# RHX-NYFK-SCH21V1_01.net
KiCad netlist of a schematic drawn in Altium Designer
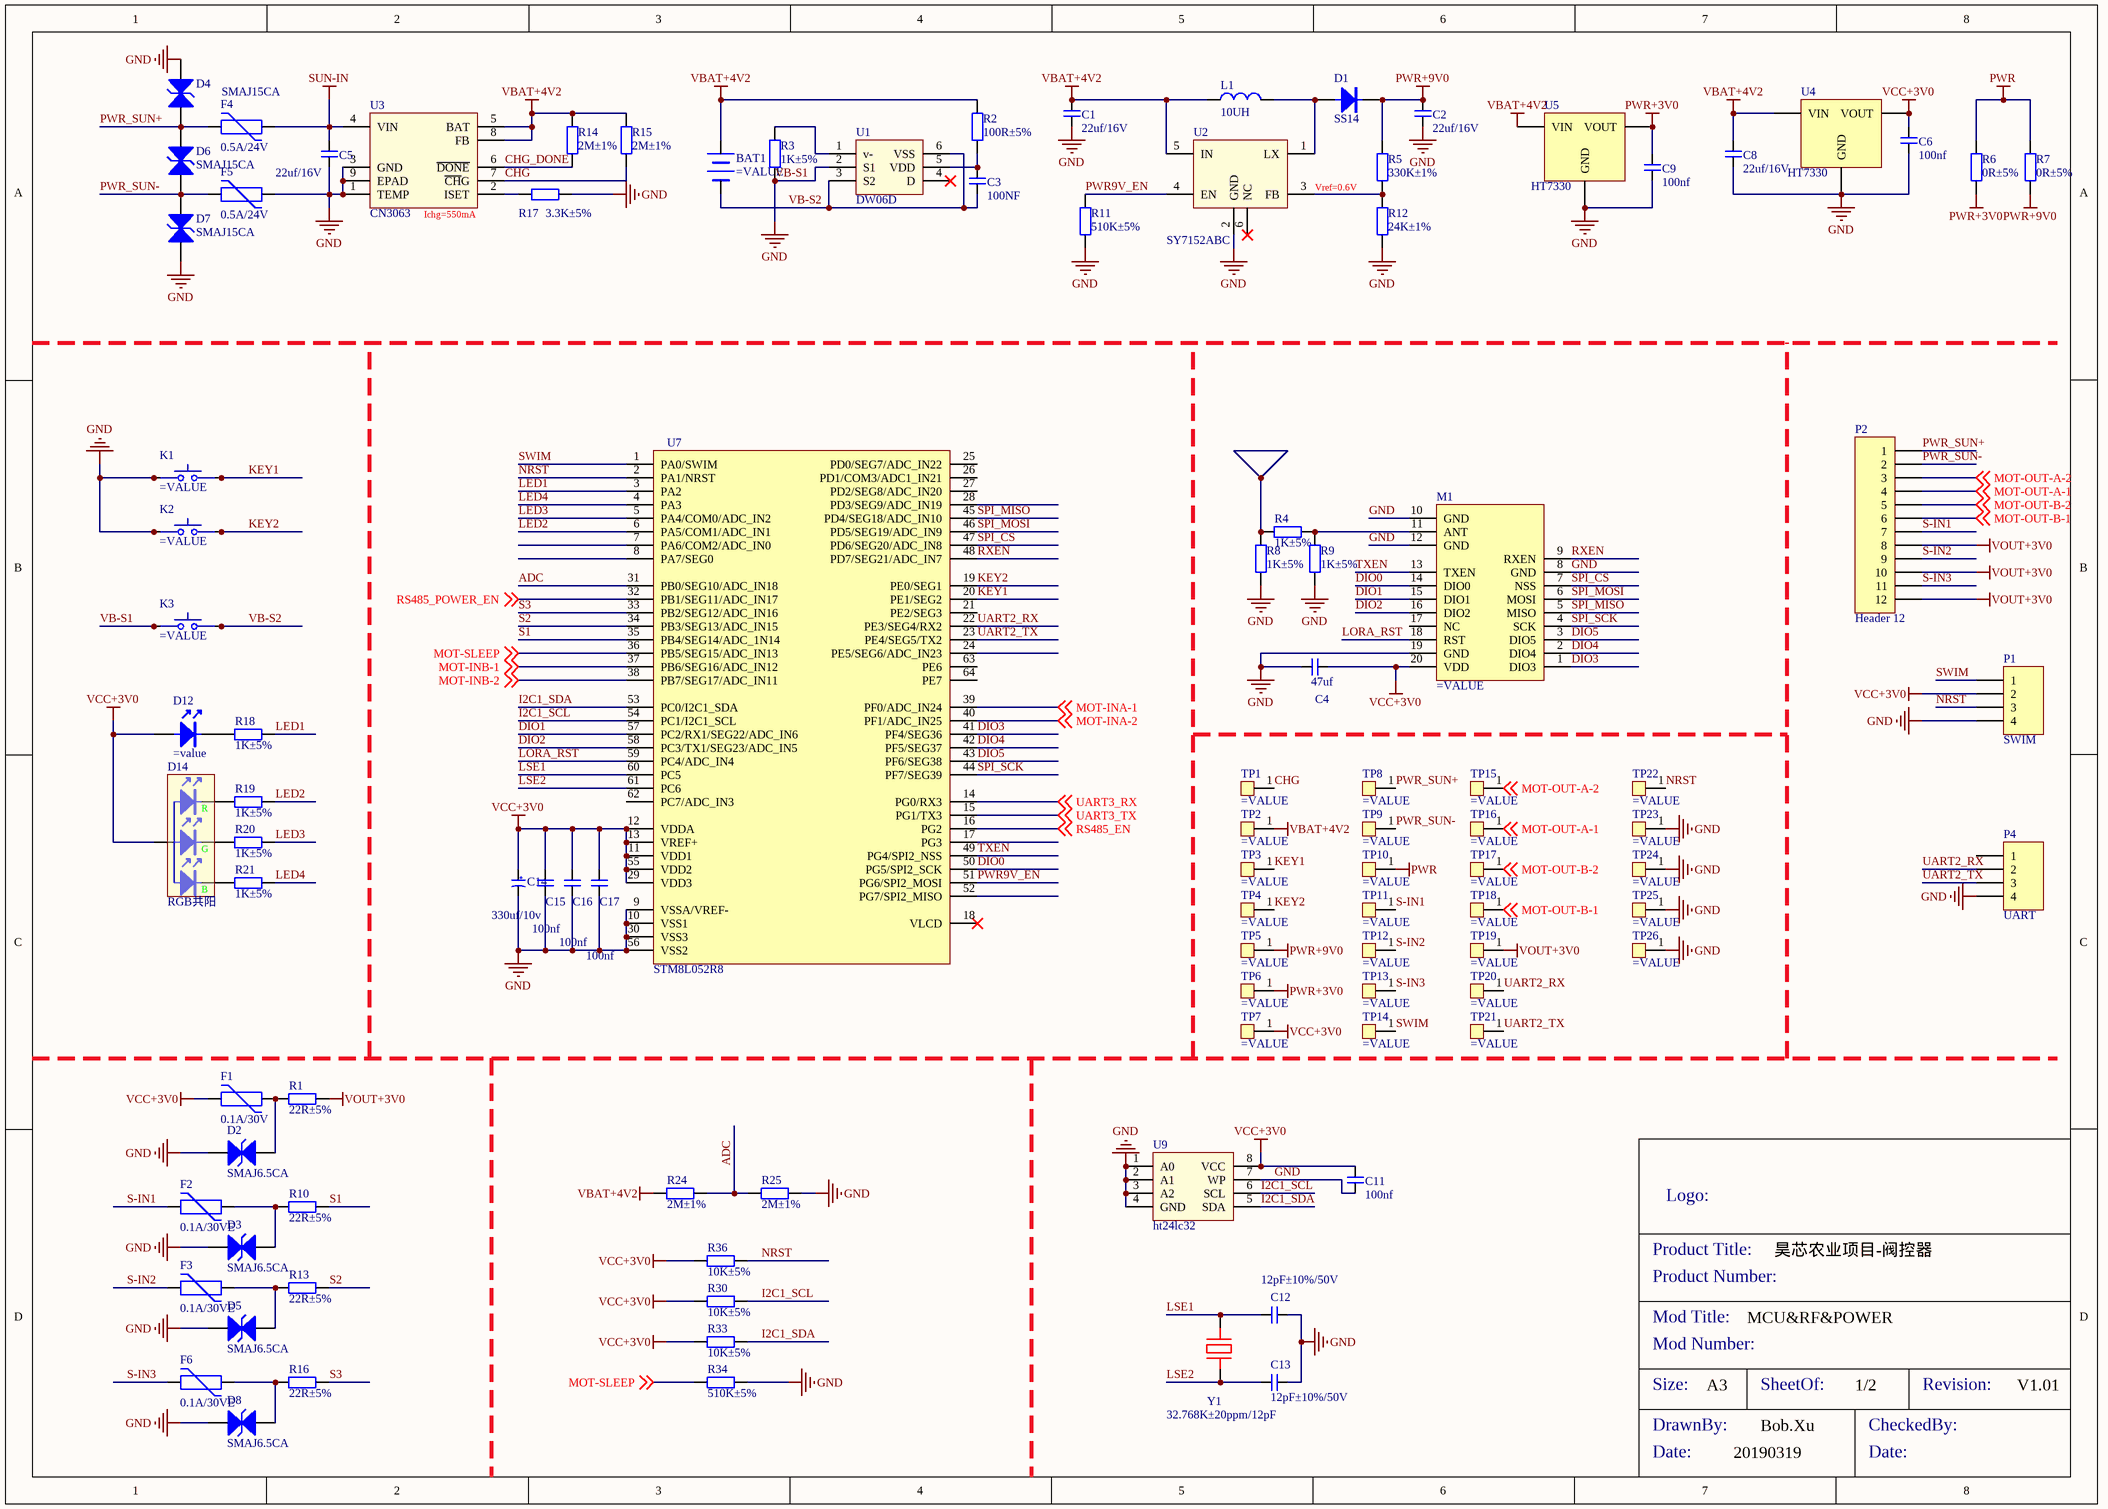
[diagram p0: RHX-NYFK-SCH21V1.01.SchDoc]

(export (version "E")
  (design (tool "Eeschema 10.0.6"))
  (components
    (comp (ref "BAT1") (value "~") (footprint "HDR1X2") (libsource (lib "瑞臻信息") (part "BAT")))
    (comp (ref "C1")
      (value "22uf/16V")
      (footprint "瑞臻信息:c1206")
      (description "无极性电容")
      (libsource (lib "瑞臻信息") (part "无极性电容"))
    )
    (comp (ref "C2")
      (value "22uf/16V")
      (footprint "瑞臻信息:c1206")
      (description "无极性电容")
      (libsource (lib "瑞臻信息") (part "无极性电容"))
    )
    (comp (ref "C3")
      (value "100NF")
      (footprint "C0402")
      (description "无极性电容")
      (libsource (lib "瑞臻信息") (part "无极性电容"))
    )
    (comp (ref "C4")
      (value "47uf")
      (footprint "瑞臻信息:C1206")
      (description "无极性电容")
      (libsource (lib "瑞臻信息") (part "无极性电容"))
    )
    (comp (ref "C5")
      (value "22uf/16V")
      (footprint "瑞臻信息:c1206")
      (description "无极性电容")
      (libsource (lib "瑞臻信息") (part "无极性电容"))
    )
    (comp (ref "C6")
      (value "100nf")
      (footprint "瑞臻信息:c0402")
      (description "无极性电容")
      (libsource (lib "瑞臻信息") (part "无极性电容"))
    )
    (comp (ref "C8")
      (value "22uf/16V")
      (footprint "瑞臻信息:c1206")
      (description "无极性电容")
      (libsource (lib "瑞臻信息") (part "无极性电容"))
    )
    (comp (ref "C9")
      (value "100nf")
      (footprint "瑞臻信息:c0402")
      (description "无极性电容")
      (libsource (lib "瑞臻信息") (part "无极性电容"))
    )
    (comp (ref "C11")
      (value "100nf")
      (footprint "C0402")
      (description "无极性电容")
      (libsource (lib "瑞臻信息") (part "无极性电容"))
    )
    (comp (ref "C12")
      (value "12pF±10%/50V")
      (footprint "C0402")
      (description "无极性电容")
      (libsource (lib "瑞臻信息") (part "无极性电容"))
    )
    (comp (ref "C13")
      (value "12pF±10%/50V")
      (footprint "C0402")
      (description "无极性电容")
      (libsource (lib "瑞臻信息") (part "无极性电容"))
    )
    (comp (ref "C14")
      (value "330uf/10v")
      (footprint "CAP_2P_2R5_D6R3H11_W")
      (description "极性电容")
      (libsource (lib "瑞臻信息") (part "极性电容"))
    )
    (comp (ref "C15")
      (value "100nf")
      (footprint "C0402")
      (description "无极性电容")
      (libsource (lib "瑞臻信息") (part "无极性电容"))
    )
    (comp (ref "C16")
      (value "100nf")
      (footprint "C0402")
      (description "无极性电容")
      (libsource (lib "瑞臻信息") (part "无极性电容"))
    )
    (comp (ref "C17")
      (value "100nf")
      (footprint "C0402")
      (description "无极性电容")
      (libsource (lib "瑞臻信息") (part "无极性电容"))
    )
    (comp (ref "D1")
      (value "SS14")
      (footprint "SMA_2P_2R8X4R6")
      (description "普通二极管")
      (libsource (lib "瑞臻信息") (part "普通二极管"))
    )
    (comp (ref "D2")
      (value "SMAJ6.5CA")
      (footprint "SMA_2P_2R8X4R6")
      (description "双向TVS管")
      (libsource (lib "瑞臻信息") (part "双向TVS管"))
    )
    (comp (ref "D3")
      (value "SMAJ6.5CA")
      (footprint "SMA_2P_2R8X4R6")
      (description "双向TVS管")
      (libsource (lib "瑞臻信息") (part "双向TVS管"))
    )
    (comp (ref "D4")
      (value "SMAJ15CA")
      (footprint "SMA_2P_2R8X4R6")
      (description "双向TVS管")
      (libsource (lib "瑞臻信息") (part "双向TVS管"))
    )
    (comp (ref "D5")
      (value "SMAJ6.5CA")
      (footprint "SMA_2P_2R8X4R6")
      (description "双向TVS管")
      (libsource (lib "瑞臻信息") (part "双向TVS管"))
    )
    (comp (ref "D6")
      (value "SMAJ15CA")
      (footprint "SMA_2P_2R8X4R6")
      (description "双向TVS管")
      (libsource (lib "瑞臻信息") (part "双向TVS管"))
    )
    (comp (ref "D7")
      (value "SMAJ15CA")
      (footprint "SMA_2P_2R8X4R6")
      (description "双向TVS管")
      (libsource (lib "瑞臻信息") (part "双向TVS管"))
    )
    (comp (ref "D8")
      (value "SMAJ6.5CA")
      (footprint "SMA_2P_2R8X4R6")
      (description "双向TVS管")
      (libsource (lib "瑞臻信息") (part "双向TVS管"))
    )
    (comp (ref "D12")
      (value "~")
      (footprint "LED_2P_2R54_D5X8R7")
      (description "单LED")
      (libsource (lib "瑞臻信息") (part "单LED"))
    )
    (comp (ref "D14")
      (value "RGB共阳")
      (footprint "DIP_LED_4P_RGB_1R3_D5")
      (libsource (lib "瑞臻信息") (part "LED-RGB-共阳"))
    )
    (comp (ref "F1") (value "0.1A/30V") (footprint "FUSE1210") (libsource (lib "瑞臻信息") (part "PPTC")))
    (comp (ref "F2") (value "0.1A/30VE") (footprint "FUSE1210") (libsource (lib "瑞臻信息") (part "PPTC")))
    (comp (ref "F3") (value "0.1A/30VE") (footprint "FUSE1210") (libsource (lib "瑞臻信息") (part "PPTC")))
    (comp (ref "F4") (value "0.5A/24V") (footprint "FUSE1210") (libsource (lib "瑞臻信息") (part "PPTC")))
    (comp (ref "F5") (value "0.5A/24V") (footprint "FUSE1210") (libsource (lib "瑞臻信息") (part "PPTC")))
    (comp (ref "F6") (value "0.1A/30VE") (footprint "FUSE1210") (libsource (lib "瑞臻信息") (part "PPTC")))
    (comp (ref "K1")
      (value "~")
      (footprint "DIP_SW_4P_6R0X6R0_P")
      (description "4脚贴片按键")
      (libsource (lib "瑞臻信息") (part "SKRWAEE030"))
    )
    (comp (ref "K2")
      (value "~")
      (footprint "DIP_SW_4P_6R0X6R0_P")
      (description "4脚贴片按键")
      (libsource (lib "瑞臻信息") (part "SKRWAEE030"))
    )
    (comp (ref "K3")
      (value "~")
      (footprint "DIP_SW_4P_6R0X6R0_P")
      (description "4脚贴片按键")
      (libsource (lib "瑞臻信息") (part "SKRWAEE030"))
    )
    (comp (ref "L1")
      (value "10UH")
      (footprint "SMD_INC_2P_4R0X4R0")
      (description "普通电感")
      (libsource (lib "瑞臻信息") (part "普通电感"))
    )
    (comp (ref "M1") (value "~") (footprint "LORA_PIN_1") (libsource (lib "瑞臻信息") (part "LORA_PIN_1")))
    (comp (ref "P1")
      (value "SWIM")
      (footprint "HDR1X4")
      (description "Header, 4-Pin")
      (libsource (lib "Miscellaneous Connectors") (part "Header 4"))
    )
    (comp (ref "P2")
      (value "Header 12")
      (footprint "KF301_12P_5R08")
      (description "Header, 12-Pin")
      (libsource (lib "Miscellaneous Connectors") (part "Header 12"))
    )
    (comp (ref "P4")
      (value "UART")
      (footprint "HDR1X4")
      (description "Header, 4-Pin")
      (libsource (lib "Miscellaneous Connectors") (part "Header 4"))
    )
    (comp (ref "R1")
      (value "22R±5%")
      (footprint "R0402")
      (description "电阻-4.7R±5%-1/16W-0402")
      (fields (field (name "PART NUMBER") "1.2.03.01.0573"))
      (libsource (lib "檀木科技") (part "普通电阻"))
    )
    (comp (ref "R2")
      (value "100R±5%")
      (footprint "R0402")
      (description "电阻-4.7R±5%-1/16W-0402")
      (fields (field (name "PART NUMBER") "1.2.03.01.0573"))
      (libsource (lib "") (part "普通电阻_2"))
    )
    (comp (ref "R3")
      (value "1K±5%")
      (footprint "R0402")
      (description "电阻-4.7R±5%-1/16W-0402")
      (fields (field (name "PART NUMBER") "1.2.03.01.0573"))
      (libsource (lib "") (part "普通电阻_2"))
    )
    (comp (ref "R4")
      (value "1K±5%")
      (footprint "R0402")
      (description "电阻-10K±5%-1/16W-0402")
      (fields (field (name "PART NUMBER") "1.2.03.01.0012"))
      (libsource (lib "") (part "普通电阻_2"))
    )
    (comp (ref "R5")
      (value "330K±1%")
      (footprint "R0402")
      (description "电阻-10K±5%-1/16W-0402")
      (fields (field (name "PART NUMBER") "1.2.03.01.0012"))
      (libsource (lib "") (part "普通电阻_2"))
    )
    (comp (ref "R6")
      (value "0R±5%")
      (footprint "R0603")
      (description "电阻-10K±5%-1/16W-0402")
      (fields (field (name "PART NUMBER") "1.2.03.01.0012"))
      (libsource (lib "") (part "普通电阻_2"))
    )
    (comp (ref "R7")
      (value "0R±5%")
      (footprint "R0603")
      (description "电阻-10K±5%-1/16W-0402")
      (fields (field (name "PART NUMBER") "1.2.03.01.0012"))
      (libsource (lib "") (part "普通电阻_2"))
    )
    (comp (ref "R8")
      (value "1K±5%")
      (footprint "R0402")
      (description "电阻-10K±5%-1/16W-0402")
      (fields (field (name "PART NUMBER") "1.2.03.01.0012"))
      (libsource (lib "檀木科技") (part "普通电阻"))
    )
    (comp (ref "R9")
      (value "1K±5%")
      (footprint "R0402")
      (description "电阻-10K±5%-1/16W-0402")
      (fields (field (name "PART NUMBER") "1.2.03.01.0012"))
      (libsource (lib "檀木科技") (part "普通电阻"))
    )
    (comp (ref "R10")
      (value "22R±5%")
      (footprint "R0402")
      (description "电阻-4.7R±5%-1/16W-0402")
      (fields (field (name "PART NUMBER") "1.2.03.01.0573"))
      (libsource (lib "檀木科技") (part "普通电阻"))
    )
    (comp (ref "R11")
      (value "510K±5%")
      (footprint "R0402")
      (description "电阻-10K±5%-1/16W-0402")
      (fields (field (name "PART NUMBER") "1.2.03.01.0012"))
      (libsource (lib "") (part "普通电阻_2"))
    )
    (comp (ref "R12")
      (value "24K±1%")
      (footprint "R0402")
      (description "电阻-10K±5%-1/16W-0402")
      (fields (field (name "PART NUMBER") "1.2.03.01.0012"))
      (libsource (lib "") (part "普通电阻_2"))
    )
    (comp (ref "R13")
      (value "22R±5%")
      (footprint "R0402")
      (description "电阻-4.7R±5%-1/16W-0402")
      (fields (field (name "PART NUMBER") "1.2.03.01.0573"))
      (libsource (lib "檀木科技") (part "普通电阻"))
    )
    (comp (ref "R14")
      (value "2M±1%")
      (footprint "R0402")
      (description "电阻-10K±5%-1/16W-0402")
      (fields (field (name "PART NUMBER") "1.2.03.01.0012"))
      (libsource (lib "") (part "普通电阻_3"))
    )
    (comp (ref "R15")
      (value "2M±1%")
      (footprint "R0402")
      (description "电阻-10K±5%-1/16W-0402")
      (fields (field (name "PART NUMBER") "1.2.03.01.0012"))
      (libsource (lib "") (part "普通电阻_3"))
    )
    (comp (ref "R16")
      (value "22R±5%")
      (footprint "R0402")
      (description "电阻-4.7R±5%-1/16W-0402")
      (fields (field (name "PART NUMBER") "1.2.03.01.0573"))
      (libsource (lib "檀木科技") (part "普通电阻"))
    )
    (comp (ref "R17")
      (value "3.3K±5%")
      (footprint "R0402")
      (description "电阻-4.7R±5%-1/16W-0402")
      (fields (field (name "PART NUMBER") "1.2.03.01.0573"))
      (libsource (lib "") (part "普通电阻_1"))
    )
    (comp (ref "R18")
      (value "1K±5%")
      (footprint "R0402")
      (description "电阻-4.7R±5%-1/16W-0402")
      (fields (field (name "PART NUMBER") "1.2.03.01.0573"))
      (libsource (lib "檀木科技") (part "普通电阻"))
    )
    (comp (ref "R19")
      (value "1K±5%")
      (footprint "R0402")
      (description "电阻-4.7R±5%-1/16W-0402")
      (fields (field (name "PART NUMBER") "1.2.03.01.0573"))
      (libsource (lib "檀木科技") (part "普通电阻"))
    )
    (comp (ref "R20")
      (value "1K±5%")
      (footprint "R0402")
      (description "电阻-4.7R±5%-1/16W-0402")
      (fields (field (name "PART NUMBER") "1.2.03.01.0573"))
      (libsource (lib "檀木科技") (part "普通电阻"))
    )
    (comp (ref "R21")
      (value "1K±5%")
      (footprint "R0402")
      (description "电阻-4.7R±5%-1/16W-0402")
      (fields (field (name "PART NUMBER") "1.2.03.01.0573"))
      (libsource (lib "檀木科技") (part "普通电阻"))
    )
    (comp (ref "R24")
      (value "2M±1%")
      (footprint "R0402")
      (description "电阻-10K±5%-1/16W-0402")
      (fields (field (name "PART NUMBER") "1.2.03.01.0012"))
      (libsource (lib "") (part "普通电阻_1"))
    )
    (comp (ref "R25")
      (value "2M±1%")
      (footprint "R0402")
      (description "电阻-10K±5%-1/16W-0402")
      (fields (field (name "PART NUMBER") "1.2.03.01.0012"))
      (libsource (lib "") (part "普通电阻_1"))
    )
    (comp (ref "R30")
      (value "10K±5%")
      (footprint "R0402")
      (description "电阻-10K±5%-1/16W-0402")
      (fields (field (name "PART NUMBER") "1.2.03.01.0012"))
      (libsource (lib "檀木科技") (part "普通电阻"))
    )
    (comp (ref "R33")
      (value "10K±5%")
      (footprint "R0402")
      (description "电阻-10K±5%-1/16W-0402")
      (fields (field (name "PART NUMBER") "1.2.03.01.0012"))
      (libsource (lib "檀木科技") (part "普通电阻"))
    )
    (comp (ref "R34")
      (value "510K±5%")
      (footprint "R0402")
      (description "电阻-10K±5%-1/16W-0402")
      (fields (field (name "PART NUMBER") "1.2.03.01.0012"))
      (libsource (lib "檀木科技") (part "普通电阻"))
    )
    (comp (ref "R36")
      (value "10K±5%")
      (footprint "R0402")
      (description "电阻-10K±5%-1/16W-0402")
      (fields (field (name "PART NUMBER") "1.2.03.01.0012"))
      (libsource (lib "檀木科技") (part "普通电阻"))
    )
    (comp (ref "TP1")
      (value "~")
      (footprint "TP_D1R25")
      (description "测试点")
      (libsource (lib "瑞臻信息") (part "Test_Point"))
    )
    (comp (ref "TP2")
      (value "~")
      (footprint "TP_D1R25")
      (description "测试点")
      (libsource (lib "瑞臻信息") (part "Test_Point"))
    )
    (comp (ref "TP3")
      (value "~")
      (footprint "TP_D1R25")
      (description "测试点")
      (libsource (lib "瑞臻信息") (part "Test_Point"))
    )
    (comp (ref "TP4")
      (value "~")
      (footprint "TP_D1R25")
      (description "测试点")
      (libsource (lib "瑞臻信息") (part "Test_Point"))
    )
    (comp (ref "TP5")
      (value "~")
      (footprint "TP_D1R25")
      (description "测试点")
      (libsource (lib "瑞臻信息") (part "Test_Point"))
    )
    (comp (ref "TP6")
      (value "~")
      (footprint "TP_D1R25")
      (description "测试点")
      (libsource (lib "瑞臻信息") (part "Test_Point"))
    )
    (comp (ref "TP7")
      (value "~")
      (footprint "TP_D1R25")
      (description "测试点")
      (libsource (lib "瑞臻信息") (part "Test_Point"))
    )
    (comp (ref "TP8")
      (value "~")
      (footprint "TP_D1R25")
      (description "测试点")
      (libsource (lib "瑞臻信息") (part "Test_Point"))
    )
    (comp (ref "TP9")
      (value "~")
      (footprint "TP_D1R25")
      (description "测试点")
      (libsource (lib "瑞臻信息") (part "Test_Point"))
    )
    (comp (ref "TP10")
      (value "~")
      (footprint "TP_D1R25")
      (description "测试点")
      (libsource (lib "瑞臻信息") (part "Test_Point"))
    )
    (comp (ref "TP11")
      (value "~")
      (footprint "TP_D1R25")
      (description "测试点")
      (libsource (lib "瑞臻信息") (part "Test_Point"))
    )
    (comp (ref "TP12")
      (value "~")
      (footprint "TP_D1R25")
      (description "测试点")
      (libsource (lib "瑞臻信息") (part "Test_Point"))
    )
    (comp (ref "TP13")
      (value "~")
      (footprint "TP_D1R25")
      (description "测试点")
      (libsource (lib "瑞臻信息") (part "Test_Point"))
    )
    (comp (ref "TP14")
      (value "~")
      (footprint "TP_D1R25")
      (description "测试点")
      (libsource (lib "瑞臻信息") (part "Test_Point"))
    )
    (comp (ref "TP15")
      (value "~")
      (footprint "TP_D1R25")
      (description "测试点")
      (libsource (lib "瑞臻信息") (part "Test_Point"))
    )
    (comp (ref "TP16")
      (value "~")
      (footprint "TP_D1R25")
      (description "测试点")
      (libsource (lib "瑞臻信息") (part "Test_Point"))
    )
    (comp (ref "TP17")
      (value "~")
      (footprint "TP_D1R25")
      (description "测试点")
      (libsource (lib "瑞臻信息") (part "Test_Point"))
    )
    (comp (ref "TP18")
      (value "~")
      (footprint "TP_D1R25")
      (description "测试点")
      (libsource (lib "瑞臻信息") (part "Test_Point"))
    )
    (comp (ref "TP19")
      (value "~")
      (footprint "TP_D1R25")
      (description "测试点")
      (libsource (lib "瑞臻信息") (part "Test_Point"))
    )
    (comp (ref "TP20")
      (value "~")
      (footprint "TP_D1R25")
      (description "测试点")
      (libsource (lib "瑞臻信息") (part "Test_Point"))
    )
    (comp (ref "TP21")
      (value "~")
      (footprint "TP_D1R25")
      (description "测试点")
      (libsource (lib "瑞臻信息") (part "Test_Point"))
    )
    (comp (ref "TP22")
      (value "~")
      (footprint "TP_D1R25")
      (description "测试点")
      (libsource (lib "瑞臻信息") (part "Test_Point"))
    )
    (comp (ref "TP23")
      (value "~")
      (footprint "TP_D1R25")
      (description "测试点")
      (libsource (lib "瑞臻信息") (part "Test_Point"))
    )
    (comp (ref "TP24")
      (value "~")
      (footprint "TP_D1R25")
      (description "测试点")
      (libsource (lib "瑞臻信息") (part "Test_Point"))
    )
    (comp (ref "TP25")
      (value "~")
      (footprint "TP_D1R25")
      (description "测试点")
      (libsource (lib "瑞臻信息") (part "Test_Point"))
    )
    (comp (ref "TP26")
      (value "~")
      (footprint "TP_D1R25")
      (description "测试点")
      (libsource (lib "瑞臻信息") (part "Test_Point"))
    )
    (comp (ref "U1")
      (value "DW06D")
      (footprint "SOT23_6P_0R95_1R6X2R9")
      (libsource (lib "瑞臻信息") (part "DW06D"))
    )
    (comp (ref "U2")
      (value "SY7152ABC")
      (footprint "SOT23_6P_0R95_1R6X2R9")
      (libsource (lib "瑞臻信息") (part "SY7152"))
    )
    (comp (ref "U3")
      (value "CN3063")
      (footprint "SOP_8P_1R27_3R9X4R9_P")
      (libsource (lib "瑞臻信息") (part "CN3063"))
    )
    (comp (ref "U4")
      (value "HT7330")
      (footprint "SOT89_3P_1R5_2R5X4R5")
      (libsource (lib "瑞臻信息") (part "HT73XX"))
    )
    (comp (ref "U5")
      (value "HT7330")
      (footprint "SOT89_3P_1R5_2R5X4R5")
      (libsource (lib "瑞臻信息") (part "HT73XX"))
    )
    (comp (ref "U7")
      (value "STM8L052R8")
      (footprint "LQFP_64P_0R5_10R0X10R0")
      (description "MCU_STM8L052R8_16MHz_Flash/64Kb_RAM/4Kb_8位_E2PROM/256B_LCD8X24_LQFP64")
      (fields (field (name "PART NUMBER") "1.2.18.01.0001"))
      (libsource (lib "瑞臻信息") (part "STM8L052R8"))
    )
    (comp (ref "U9")
      (value "ht24lc32")
      (footprint "SOP_8P_1R27_3R9X4R9")
      (libsource (lib "瑞臻信息") (part "24CXX"))
    )
    (comp (ref "Y1")
      (value "32.768K±20ppm/12pF")
      (footprint "SMD_Crystal_2P_1R5X3R2")
      (description "两脚晶体谐振器")
      (libsource (lib "瑞臻信息") (part "两脚晶体谐振器"))
    )
  )
  (nets
    (net (code "1") (name "/ADC") (class "Default")
      (node (ref "R24") (pin "2") (pinfunction "2_2") (pintype "passive"))
      (node (ref "R25") (pin "1") (pinfunction "1_1") (pintype "passive"))
      (node (ref "U7") (pin "31") (pinfunction "PB0/SEG10/ADC_IN18_31") (pintype "passive"))
    )
    (net (code "2") (name "/CHG") (class "Default")
      (node (ref "R15") (pin "1") (pinfunction "1_1") (pintype "passive"))
      (node (ref "TP1") (pin "1") (pinfunction "1_1") (pintype "passive"))
      (node (ref "U3") (pin "7") (pinfunction "~{CH}G_7") (pintype "passive"))
    )
    (net (code "3") (name "/CHG_DONE") (class "Default")
      (node (ref "R14") (pin "1") (pinfunction "1_1") (pintype "passive"))
      (node (ref "U3") (pin "6") (pinfunction "~{DONE}_6") (pintype "passive"))
    )
    (net (code "4") (name "/DIO0") (class "Default")
      (node (ref "M1") (pin "14") (pinfunction "DIO0_14") (pintype "passive"))
      (node (ref "U7") (pin "50") (pinfunction "PG5/SPI2_SCK_50") (pintype "passive"))
    )
    (net (code "5") (name "/DIO1") (class "Default")
      (node (ref "M1") (pin "15") (pinfunction "DIO1_15") (pintype "passive"))
      (node (ref "U7") (pin "57") (pinfunction "PC2/RX1/SEG22/ADC_IN6_57") (pintype "passive"))
    )
    (net (code "6") (name "/DIO2") (class "Default")
      (node (ref "M1") (pin "16") (pinfunction "DIO2_16") (pintype "passive"))
      (node (ref "U7") (pin "58") (pinfunction "PC3/TX1/SEG23/ADC_IN5_58") (pintype "passive"))
    )
    (net (code "7") (name "/DIO3") (class "Default")
      (node (ref "M1") (pin "1") (pinfunction "DIO3_1") (pintype "passive"))
      (node (ref "U7") (pin "41") (pinfunction "PF4/SEG36_41") (pintype "passive"))
    )
    (net (code "8") (name "/DIO4") (class "Default")
      (node (ref "M1") (pin "2") (pinfunction "DIO4_2") (pintype "passive"))
      (node (ref "U7") (pin "42") (pinfunction "PF5/SEG37_42") (pintype "passive"))
    )
    (net (code "9") (name "/DIO5") (class "Default")
      (node (ref "M1") (pin "3") (pinfunction "DIO5_3") (pintype "passive"))
      (node (ref "U7") (pin "43") (pinfunction "PF6/SEG38_43") (pintype "passive"))
    )
    (net (code "10") (name "/I2C1_SCL") (class "Default")
      (node (ref "R30") (pin "1") (pinfunction "1_1") (pintype "passive"))
      (node (ref "U7") (pin "54") (pinfunction "PC1/I2C1_SCL_54") (pintype "passive"))
      (node (ref "U9") (pin "6") (pinfunction "SCL_6") (pintype "passive"))
    )
    (net (code "11") (name "/I2C1_SDA") (class "Default")
      (node (ref "R33") (pin "1") (pinfunction "1_1") (pintype "passive"))
      (node (ref "U7") (pin "53") (pinfunction "PC0/I2C1_SDA_53") (pintype "passive"))
      (node (ref "U9") (pin "5") (pinfunction "SDA_5") (pintype "passive"))
    )
    (net (code "12") (name "/KEY1") (class "Default")
      (node (ref "K1") (pin "2") (pinfunction "2_2") (pintype "passive"))
      (node (ref "K1") (pin "4") (pinfunction "4_4") (pintype "passive"))
      (node (ref "TP3") (pin "1") (pinfunction "1_1") (pintype "passive"))
      (node (ref "U7") (pin "20") (pinfunction "PE1/SEG2_20") (pintype "passive"))
    )
    (net (code "13") (name "/KEY2") (class "Default")
      (node (ref "K2") (pin "2") (pinfunction "2_2") (pintype "passive"))
      (node (ref "K2") (pin "4") (pinfunction "4_4") (pintype "passive"))
      (node (ref "TP4") (pin "1") (pinfunction "1_1") (pintype "passive"))
      (node (ref "U7") (pin "19") (pinfunction "PE0/SEG1_19") (pintype "passive"))
    )
    (net (code "14") (name "/LED1") (class "Default")
      (node (ref "R18") (pin "1") (pinfunction "1_1") (pintype "passive"))
      (node (ref "U7") (pin "3") (pinfunction "PA2_3") (pintype "passive"))
    )
    (net (code "15") (name "/LED2") (class "Default")
      (node (ref "R19") (pin "1") (pinfunction "1_1") (pintype "passive"))
      (node (ref "U7") (pin "6") (pinfunction "PA5/COM1/ADC_IN1_6") (pintype "passive"))
    )
    (net (code "16") (name "/LED3") (class "Default")
      (node (ref "R20") (pin "1") (pinfunction "1_1") (pintype "passive"))
      (node (ref "U7") (pin "5") (pinfunction "PA4/COM0/ADC_IN2_5") (pintype "passive"))
    )
    (net (code "17") (name "/LED4") (class "Default")
      (node (ref "R21") (pin "1") (pinfunction "1_1") (pintype "passive"))
      (node (ref "U7") (pin "4") (pinfunction "PA3_4") (pintype "passive"))
    )
    (net (code "18") (name "/LORA_RST") (class "Default")
      (node (ref "M1") (pin "18") (pinfunction "RST_18") (pintype "passive"))
      (node (ref "U7") (pin "59") (pinfunction "PC4/ADC_IN4_59") (pintype "passive"))
    )
    (net (code "19") (name "/LSE1") (class "Default")
      (node (ref "C12") (pin "2") (pinfunction "2_2") (pintype "passive"))
      (node (ref "U7") (pin "60") (pinfunction "PC5_60") (pintype "passive"))
      (node (ref "Y1") (pin "2") (pinfunction "2_2") (pintype "passive"))
    )
    (net (code "20") (name "/LSE2") (class "Default")
      (node (ref "C13") (pin "2") (pinfunction "2_2") (pintype "passive"))
      (node (ref "U7") (pin "61") (pinfunction "PC6_61") (pintype "passive"))
      (node (ref "Y1") (pin "1") (pinfunction "1_1") (pintype "passive"))
    )
    (net (code "21") (name "/NRST") (class "Default")
      (node (ref "P1") (pin "3") (pinfunction "3_3") (pintype "passive"))
      (node (ref "R36") (pin "1") (pinfunction "1_1") (pintype "passive"))
      (node (ref "TP22") (pin "1") (pinfunction "1_1") (pintype "passive"))
      (node (ref "U7") (pin "2") (pinfunction "PA1/NRST_2") (pintype "passive"))
    )
    (net (code "22") (name "/PWR9V_EN") (class "Default")
      (node (ref "R11") (pin "1") (pinfunction "1_1") (pintype "passive"))
      (node (ref "U2") (pin "4") (pinfunction "EN_4") (pintype "passive"))
      (node (ref "U7") (pin "51") (pinfunction "PG6/SPI2_MOSI_51") (pintype "passive"))
    )
    (net (code "23") (name "/PWR_SUN+") (class "Default")
      (node (ref "D4") (pin "1") (pinfunction "A_1") (pintype "passive"))
      (node (ref "D6") (pin "2") (pinfunction "K_2") (pintype "passive"))
      (node (ref "F4") (pin "1") (pinfunction "1_1") (pintype "passive"))
      (node (ref "P2") (pin "1") (pinfunction "1_1") (pintype "passive"))
      (node (ref "TP8") (pin "1") (pinfunction "1_1") (pintype "passive"))
    )
    (net (code "24") (name "/PWR_SUN-") (class "Default")
      (node (ref "D6") (pin "1") (pinfunction "A_1") (pintype "passive"))
      (node (ref "D7") (pin "2") (pinfunction "K_2") (pintype "passive"))
      (node (ref "F5") (pin "1") (pinfunction "1_1") (pintype "passive"))
      (node (ref "P2") (pin "2") (pinfunction "2_2") (pintype "passive"))
      (node (ref "TP9") (pin "1") (pinfunction "1_1") (pintype "passive"))
    )
    (net (code "25") (name "/RXEN") (class "Default")
      (node (ref "M1") (pin "9") (pinfunction "RXEN_9") (pintype "passive"))
      (node (ref "U7") (pin "48") (pinfunction "PD7/SEG21/ADC_IN7_48") (pintype "passive"))
    )
    (net (code "26") (name "/S-IN1") (class "Default")
      (node (ref "F2") (pin "1") (pinfunction "1_1") (pintype "passive"))
      (node (ref "P2") (pin "7") (pinfunction "7_7") (pintype "passive"))
      (node (ref "TP11") (pin "1") (pinfunction "1_1") (pintype "passive"))
    )
    (net (code "27") (name "/S-IN2") (class "Default")
      (node (ref "F3") (pin "1") (pinfunction "1_1") (pintype "passive"))
      (node (ref "P2") (pin "9") (pinfunction "9_9") (pintype "passive"))
      (node (ref "TP12") (pin "1") (pinfunction "1_1") (pintype "passive"))
    )
    (net (code "28") (name "/S-IN3") (class "Default")
      (node (ref "F6") (pin "1") (pinfunction "1_1") (pintype "passive"))
      (node (ref "P2") (pin "11") (pinfunction "11_11") (pintype "passive"))
      (node (ref "TP13") (pin "1") (pinfunction "1_1") (pintype "passive"))
    )
    (net (code "29") (name "/S1") (class "Default")
      (node (ref "R10") (pin "1") (pinfunction "1_1") (pintype "passive"))
      (node (ref "U7") (pin "35") (pinfunction "PB4/SEG14/ADC_1N14_35") (pintype "passive"))
    )
    (net (code "30") (name "/S2") (class "Default")
      (node (ref "R13") (pin "1") (pinfunction "1_1") (pintype "passive"))
      (node (ref "U7") (pin "34") (pinfunction "PB3/SEG13/ADC_IN15_34") (pintype "passive"))
    )
    (net (code "31") (name "/S3") (class "Default")
      (node (ref "R16") (pin "1") (pinfunction "1_1") (pintype "passive"))
      (node (ref "U7") (pin "33") (pinfunction "PB2/SEG12/ADC_IN16_33") (pintype "passive"))
    )
    (net (code "32") (name "/SPI_CS") (class "Default")
      (node (ref "M1") (pin "7") (pinfunction "NSS_7") (pintype "passive"))
      (node (ref "U7") (pin "47") (pinfunction "PD6/SEG20/ADC_IN8_47") (pintype "passive"))
    )
    (net (code "33") (name "/SPI_MISO") (class "Default")
      (node (ref "M1") (pin "5") (pinfunction "MISO_5") (pintype "passive"))
      (node (ref "U7") (pin "45") (pinfunction "PD4/SEG18/ADC_IN10_45") (pintype "passive"))
    )
    (net (code "34") (name "/SPI_MOSI") (class "Default")
      (node (ref "M1") (pin "6") (pinfunction "MOSI_6") (pintype "passive"))
      (node (ref "U7") (pin "46") (pinfunction "PD5/SEG19/ADC_IN9_46") (pintype "passive"))
    )
    (net (code "35") (name "/SPI_SCK") (class "Default")
      (node (ref "M1") (pin "4") (pinfunction "SCK_4") (pintype "passive"))
      (node (ref "U7") (pin "44") (pinfunction "PF7/SEG39_44") (pintype "passive"))
    )
    (net (code "36") (name "/SWIM") (class "Default")
      (node (ref "P1") (pin "1") (pinfunction "1_1") (pintype "passive"))
      (node (ref "TP14") (pin "1") (pinfunction "1_1") (pintype "passive"))
      (node (ref "U7") (pin "1") (pinfunction "PA0/SWIM_1") (pintype "passive"))
    )
    (net (code "37") (name "/TXEN") (class "Default")
      (node (ref "M1") (pin "13") (pinfunction "TXEN_13") (pintype "passive"))
      (node (ref "U7") (pin "49") (pinfunction "PG4/SPI2_NSS_49") (pintype "passive"))
    )
    (net (code "38") (name "/UART2_RX") (class "Default")
      (node (ref "P4") (pin "2") (pinfunction "2_2") (pintype "passive"))
      (node (ref "TP20") (pin "1") (pinfunction "1_1") (pintype "passive"))
      (node (ref "U7") (pin "22") (pinfunction "PE3/SEG4/RX2_22") (pintype "passive"))
    )
    (net (code "39") (name "/UART2_TX") (class "Default")
      (node (ref "P4") (pin "3") (pinfunction "3_3") (pintype "passive"))
      (node (ref "TP21") (pin "1") (pinfunction "1_1") (pintype "passive"))
      (node (ref "U7") (pin "23") (pinfunction "PE4/SEG5/TX2_23") (pintype "passive"))
    )
    (net (code "40") (name "/VB-S2") (class "Default")
      (node (ref "BAT1") (pin "2") (pintype "passive"))
      (node (ref "C3") (pin "1") (pinfunction "1_1") (pintype "passive"))
      (node (ref "K3") (pin "2") (pinfunction "2_2") (pintype "passive"))
      (node (ref "K3") (pin "4") (pinfunction "4_4") (pintype "passive"))
      (node (ref "U1") (pin "3") (pinfunction "S2_3") (pintype "passive"))
      (node (ref "U1") (pin "6") (pinfunction "VSS_6") (pintype "passive"))
    )
    (net (code "41") (name "GND") (class "Default")
      (node (ref "C1") (pin "1") (pinfunction "1_1") (pintype "passive"))
      (node (ref "C11") (pin "1") (pinfunction "1_1") (pintype "passive"))
      (node (ref "C12") (pin "1") (pinfunction "1_1") (pintype "passive"))
      (node (ref "C13") (pin "1") (pinfunction "1_1") (pintype "passive"))
      (node (ref "C14") (pin "2") (pinfunction "2_2") (pintype "passive"))
      (node (ref "C15") (pin "1") (pinfunction "1_1") (pintype "passive"))
      (node (ref "C16") (pin "1") (pinfunction "1_1") (pintype "passive"))
      (node (ref "C17") (pin "1") (pinfunction "1_1") (pintype "passive"))
      (node (ref "C2") (pin "1") (pinfunction "1_1") (pintype "passive"))
      (node (ref "C4") (pin "1") (pinfunction "1_1") (pintype "passive"))
      (node (ref "C5") (pin "1") (pinfunction "1_1") (pintype "passive"))
      (node (ref "C6") (pin "1") (pinfunction "1_1") (pintype "passive"))
      (node (ref "C8") (pin "1") (pinfunction "1_1") (pintype "passive"))
      (node (ref "C9") (pin "1") (pinfunction "1_1") (pintype "passive"))
      (node (ref "D2") (pin "1") (pinfunction "A_1") (pintype "passive"))
      (node (ref "D3") (pin "1") (pinfunction "A_1") (pintype "passive"))
      (node (ref "D4") (pin "2") (pinfunction "K_2") (pintype "passive"))
      (node (ref "D5") (pin "1") (pinfunction "A_1") (pintype "passive"))
      (node (ref "D7") (pin "1") (pinfunction "A_1") (pintype "passive"))
      (node (ref "D8") (pin "1") (pinfunction "A_1") (pintype "passive"))
      (node (ref "F5") (pin "2") (pinfunction "2_2") (pintype "passive"))
      (node (ref "K1") (pin "1") (pinfunction "1_1") (pintype "passive"))
      (node (ref "K1") (pin "3") (pinfunction "3_3") (pintype "passive"))
      (node (ref "K2") (pin "1") (pinfunction "1_1") (pintype "passive"))
      (node (ref "K2") (pin "3") (pinfunction "3_3") (pintype "passive"))
      (node (ref "K3") (pin "1") (pinfunction "1_1") (pintype "passive"))
      (node (ref "K3") (pin "3") (pinfunction "3_3") (pintype "passive"))
      (node (ref "M1") (pin "10") (pinfunction "GND_10") (pintype "passive"))
      (node (ref "M1") (pin "12") (pinfunction "GND_12") (pintype "passive"))
      (node (ref "M1") (pin "19") (pinfunction "GND_19") (pintype "passive"))
      (node (ref "M1") (pin "8") (pinfunction "GND_8") (pintype "passive"))
      (node (ref "P1") (pin "4") (pinfunction "4_4") (pintype "passive"))
      (node (ref "P4") (pin "4") (pinfunction "4_4") (pintype "passive"))
      (node (ref "R11") (pin "2") (pinfunction "2_2") (pintype "passive"))
      (node (ref "R12") (pin "2") (pinfunction "2_2") (pintype "passive"))
      (node (ref "R17") (pin "2") (pinfunction "2_2") (pintype "passive"))
      (node (ref "R25") (pin "2") (pinfunction "2_2") (pintype "passive"))
      (node (ref "R3") (pin "2") (pinfunction "2_2") (pintype "passive"))
      (node (ref "R34") (pin "1") (pinfunction "1_1") (pintype "passive"))
      (node (ref "R8") (pin "2") (pinfunction "2_2") (pintype "passive"))
      (node (ref "R9") (pin "2") (pinfunction "2_2") (pintype "passive"))
      (node (ref "TP23") (pin "1") (pinfunction "1_1") (pintype "passive"))
      (node (ref "TP24") (pin "1") (pinfunction "1_1") (pintype "passive"))
      (node (ref "TP25") (pin "1") (pinfunction "1_1") (pintype "passive"))
      (node (ref "TP26") (pin "1") (pinfunction "1_1") (pintype "passive"))
      (node (ref "U1") (pin "2") (pinfunction "S1_2") (pintype "passive"))
      (node (ref "U2") (pin "2") (pinfunction "GND_2") (pintype "passive"))
      (node (ref "U3") (pin "1") (pinfunction "TEMP_1") (pintype "passive"))
      (node (ref "U3") (pin "3") (pinfunction "GND_3") (pintype "passive"))
      (node (ref "U3") (pin "9") (pinfunction "EPAD_9") (pintype "passive"))
      (node (ref "U4") (pin "1") (pinfunction "GND_1") (pintype "passive"))
      (node (ref "U5") (pin "1") (pinfunction "GND_1") (pintype "passive"))
      (node (ref "U7") (pin "10") (pinfunction "VSS1_10") (pintype "passive"))
      (node (ref "U7") (pin "30") (pinfunction "VSS3_30") (pintype "passive"))
      (node (ref "U7") (pin "56") (pinfunction "VSS2_56") (pintype "passive"))
      (node (ref "U7") (pin "9") (pinfunction "VSSA/VREF-_9") (pintype "passive"))
      (node (ref "U9") (pin "1") (pinfunction "A0_1") (pintype "passive"))
      (node (ref "U9") (pin "2") (pinfunction "A1_2") (pintype "passive"))
      (node (ref "U9") (pin "3") (pinfunction "A2_3") (pintype "passive"))
      (node (ref "U9") (pin "4") (pinfunction "GND_4") (pintype "passive"))
      (node (ref "U9") (pin "7") (pinfunction "WP_7") (pintype "passive"))
    )
    (net (code "42") (name "MOT-INA-1") (class "Default")
      (node (ref "U7") (pin "39") (pinfunction "PF0/ADC_IN24_39") (pintype "passive"))
    )
    (net (code "43") (name "MOT-INA-2") (class "Default")
      (node (ref "U7") (pin "40") (pinfunction "PF1/ADC_IN25_40") (pintype "passive"))
    )
    (net (code "44") (name "MOT-INB-1") (class "Default")
      (node (ref "U7") (pin "37") (pinfunction "PB6/SEG16/ADC_IN12_37") (pintype "passive"))
    )
    (net (code "45") (name "MOT-INB-2") (class "Default")
      (node (ref "U7") (pin "38") (pinfunction "PB7/SEG17/ADC_IN11_38") (pintype "passive"))
    )
    (net (code "46") (name "MOT-OUT-A-1") (class "Default")
      (node (ref "P2") (pin "4") (pinfunction "4_4") (pintype "passive"))
      (node (ref "TP16") (pin "1") (pinfunction "1_1") (pintype "passive"))
    )
    (net (code "47") (name "MOT-OUT-A-2") (class "Default")
      (node (ref "P2") (pin "3") (pinfunction "3_3") (pintype "passive"))
      (node (ref "TP15") (pin "1") (pinfunction "1_1") (pintype "passive"))
    )
    (net (code "48") (name "MOT-OUT-B-1") (class "Default")
      (node (ref "P2") (pin "6") (pinfunction "6_6") (pintype "passive"))
      (node (ref "TP18") (pin "1") (pinfunction "1_1") (pintype "passive"))
    )
    (net (code "49") (name "MOT-OUT-B-2") (class "Default")
      (node (ref "P2") (pin "5") (pinfunction "5_5") (pintype "passive"))
      (node (ref "TP17") (pin "1") (pinfunction "1_1") (pintype "passive"))
    )
    (net (code "50") (name "MOT-SLEEP") (class "Default")
      (node (ref "R34") (pin "2") (pinfunction "2_2") (pintype "passive"))
      (node (ref "U7") (pin "36") (pinfunction "PB5/SEG15/ADC_IN13_36") (pintype "passive"))
    )
    (net (code "51") (name "Net-(D1-A)") (class "Default")
      (node (ref "D1") (pin "1") (pinfunction "A_1") (pintype "passive"))
      (node (ref "L1") (pin "2") (pinfunction "2_2") (pintype "passive"))
      (node (ref "U2") (pin "1") (pinfunction "LX_1") (pintype "passive"))
    )
    (net (code "52") (name "Net-(D2-K)") (class "Default")
      (node (ref "D2") (pin "2") (pinfunction "K_2") (pintype "passive"))
      (node (ref "F1") (pin "2") (pinfunction "2_2") (pintype "passive"))
      (node (ref "R1") (pin "2") (pinfunction "2_2") (pintype "passive"))
    )
    (net (code "53") (name "Net-(D3-K)") (class "Default")
      (node (ref "D3") (pin "2") (pinfunction "K_2") (pintype "passive"))
      (node (ref "F2") (pin "2") (pinfunction "2_2") (pintype "passive"))
      (node (ref "R10") (pin "2") (pinfunction "2_2") (pintype "passive"))
    )
    (net (code "54") (name "Net-(D5-K)") (class "Default")
      (node (ref "D5") (pin "2") (pinfunction "K_2") (pintype "passive"))
      (node (ref "F3") (pin "2") (pinfunction "2_2") (pintype "passive"))
      (node (ref "R13") (pin "2") (pinfunction "2_2") (pintype "passive"))
    )
    (net (code "55") (name "Net-(D8-K)") (class "Default")
      (node (ref "D8") (pin "2") (pinfunction "K_2") (pintype "passive"))
      (node (ref "F6") (pin "2") (pinfunction "2_2") (pintype "passive"))
      (node (ref "R16") (pin "2") (pinfunction "2_2") (pintype "passive"))
    )
    (net (code "56") (name "Net-(D12-K)") (class "Default")
      (node (ref "D12") (pin "2") (pinfunction "K_2") (pintype "passive"))
      (node (ref "R18") (pin "2") (pinfunction "2_2") (pintype "passive"))
    )
    (net (code "57") (name "Net-(D14-Pad1)") (class "Default")
      (node (ref "D14") (pin "1") (pinfunction "1_1") (pintype "passive"))
      (node (ref "R19") (pin "2") (pinfunction "2_2") (pintype "passive"))
    )
    (net (code "58") (name "Net-(D14-Pad3)") (class "Default")
      (node (ref "D14") (pin "3") (pinfunction "3_3") (pintype "passive"))
      (node (ref "R20") (pin "2") (pinfunction "2_2") (pintype "passive"))
    )
    (net (code "59") (name "Net-(D14-Pad4)") (class "Default")
      (node (ref "D14") (pin "4") (pinfunction "4_4") (pintype "passive"))
      (node (ref "R21") (pin "2") (pinfunction "2_2") (pintype "passive"))
    )
    (net (code "60") (name "Net-(M1-ANT)") (class "Default")
      (node (ref "M1") (pin "11") (pinfunction "ANT_11") (pintype "passive"))
      (node (ref "R4") (pin "1") (pinfunction "1_1") (pintype "passive"))
      (node (ref "R9") (pin "1") (pinfunction "1_1") (pintype "passive"))
    )
    (net (code "61") (name "Net-(R4-Pad2)") (class "Default")
      (node (ref "R4") (pin "2") (pinfunction "2_2") (pintype "passive"))
      (node (ref "R8") (pin "1") (pinfunction "1_1") (pintype "passive"))
    )
    (net (code "62") (name "Net-(U1-VDD)") (class "Default")
      (node (ref "C3") (pin "2") (pinfunction "2_2") (pintype "passive"))
      (node (ref "R2") (pin "2") (pinfunction "2_2") (pintype "passive"))
      (node (ref "U1") (pin "5") (pinfunction "VDD_5") (pintype "passive"))
    )
    (net (code "63") (name "Net-(U1-v-)") (class "Default")
      (node (ref "R3") (pin "1") (pinfunction "1_1") (pintype "passive"))
      (node (ref "U1") (pin "1") (pinfunction "v-_1") (pintype "passive"))
    )
    (net (code "64") (name "Net-(U2-FB)") (class "Default")
      (node (ref "R12") (pin "1") (pinfunction "1_1") (pintype "passive"))
      (node (ref "R5") (pin "2") (pinfunction "2_2") (pintype "passive"))
      (node (ref "U2") (pin "3") (pinfunction "FB_3") (pintype "passive"))
    )
    (net (code "65") (name "Net-(U3-ISET)") (class "Default")
      (node (ref "R17") (pin "1") (pinfunction "1_1") (pintype "passive"))
      (node (ref "U3") (pin "2") (pinfunction "ISET_2") (pintype "passive"))
    )
    (net (code "66") (name "PWR") (class "Default")
      (node (ref "R6") (pin "1") (pinfunction "1_1") (pintype "passive"))
      (node (ref "R7") (pin "1") (pinfunction "1_1") (pintype "passive"))
      (node (ref "TP10") (pin "1") (pinfunction "1_1") (pintype "passive"))
    )
    (net (code "67") (name "PWR+3V0") (class "Default")
      (node (ref "C9") (pin "2") (pinfunction "2_2") (pintype "passive"))
      (node (ref "R6") (pin "2") (pinfunction "2_2") (pintype "passive"))
      (node (ref "TP6") (pin "1") (pinfunction "1_1") (pintype "passive"))
      (node (ref "U5") (pin "3") (pinfunction "VOUT_3") (pintype "passive"))
    )
    (net (code "68") (name "PWR+9V0") (class "Default")
      (node (ref "C2") (pin "2") (pinfunction "2_2") (pintype "passive"))
      (node (ref "D1") (pin "2") (pinfunction "K_2") (pintype "passive"))
      (node (ref "R5") (pin "1") (pinfunction "1_1") (pintype "passive"))
      (node (ref "R7") (pin "2") (pinfunction "2_2") (pintype "passive"))
      (node (ref "TP5") (pin "1") (pinfunction "1_1") (pintype "passive"))
    )
    (net (code "69") (name "RS485_EN") (class "Default")
      (node (ref "U7") (pin "16") (pinfunction "PG2_16") (pintype "passive"))
    )
    (net (code "70") (name "RS485_POWER_EN") (class "Default")
      (node (ref "U7") (pin "32") (pinfunction "PB1/SEG11/ADC_IN17_32") (pintype "passive"))
    )
    (net (code "71") (name "SUN-IN") (class "Default")
      (node (ref "C5") (pin "2") (pinfunction "2_2") (pintype "passive"))
      (node (ref "F4") (pin "2") (pinfunction "2_2") (pintype "passive"))
      (node (ref "U3") (pin "4") (pinfunction "VIN_4") (pintype "passive"))
    )
    (net (code "72") (name "UART3_RX") (class "Default")
      (node (ref "U7") (pin "14") (pinfunction "PG0/RX3_14") (pintype "passive"))
    )
    (net (code "73") (name "UART3_TX") (class "Default")
      (node (ref "U7") (pin "15") (pinfunction "PG1/TX3_15") (pintype "passive"))
    )
    (net (code "74") (name "VBAT+4V2") (class "Default")
      (node (ref "BAT1") (pin "1") (pintype "passive"))
      (node (ref "C1") (pin "2") (pinfunction "2_2") (pintype "passive"))
      (node (ref "C8") (pin "2") (pinfunction "2_2") (pintype "passive"))
      (node (ref "L1") (pin "1") (pinfunction "1_1") (pintype "passive"))
      (node (ref "R14") (pin "2") (pinfunction "2_2") (pintype "passive"))
      (node (ref "R15") (pin "2") (pinfunction "2_2") (pintype "passive"))
      (node (ref "R2") (pin "1") (pinfunction "1_1") (pintype "passive"))
      (node (ref "R24") (pin "1") (pinfunction "1_1") (pintype "passive"))
      (node (ref "TP2") (pin "1") (pinfunction "1_1") (pintype "passive"))
      (node (ref "U2") (pin "5") (pinfunction "IN_5") (pintype "passive"))
      (node (ref "U3") (pin "5") (pinfunction "BAT_5") (pintype "passive"))
      (node (ref "U3") (pin "8") (pinfunction "FB_8") (pintype "passive"))
      (node (ref "U4") (pin "2") (pinfunction "VIN_2") (pintype "passive"))
      (node (ref "U5") (pin "2") (pinfunction "VIN_2") (pintype "passive"))
    )
    (net (code "75") (name "VCC+3V0") (class "Default")
      (node (ref "C11") (pin "2") (pinfunction "2_2") (pintype "passive"))
      (node (ref "C14") (pin "1") (pinfunction "1_1") (pintype "passive"))
      (node (ref "C15") (pin "2") (pinfunction "2_2") (pintype "passive"))
      (node (ref "C16") (pin "2") (pinfunction "2_2") (pintype "passive"))
      (node (ref "C17") (pin "2") (pinfunction "2_2") (pintype "passive"))
      (node (ref "C4") (pin "2") (pinfunction "2_2") (pintype "passive"))
      (node (ref "C6") (pin "2") (pinfunction "2_2") (pintype "passive"))
      (node (ref "D12") (pin "1") (pinfunction "A_1") (pintype "passive"))
      (node (ref "D14") (pin "2") (pinfunction "2_2") (pintype "passive"))
      (node (ref "F1") (pin "1") (pinfunction "1_1") (pintype "passive"))
      (node (ref "M1") (pin "20") (pinfunction "VDD_20") (pintype "passive"))
      (node (ref "P1") (pin "2") (pinfunction "2_2") (pintype "passive"))
      (node (ref "R30") (pin "2") (pinfunction "2_2") (pintype "passive"))
      (node (ref "R33") (pin "2") (pinfunction "2_2") (pintype "passive"))
      (node (ref "R36") (pin "2") (pinfunction "2_2") (pintype "passive"))
      (node (ref "TP7") (pin "1") (pinfunction "1_1") (pintype "passive"))
      (node (ref "U4") (pin "3") (pinfunction "VOUT_3") (pintype "passive"))
      (node (ref "U7") (pin "11") (pinfunction "VDD1_11") (pintype "passive"))
      (node (ref "U7") (pin "12") (pinfunction "VDDA_12") (pintype "passive"))
      (node (ref "U7") (pin "13") (pinfunction "VREF+_13") (pintype "passive"))
      (node (ref "U7") (pin "29") (pinfunction "VDD3_29") (pintype "passive"))
      (node (ref "U7") (pin "55") (pinfunction "VDD2_55") (pintype "passive"))
      (node (ref "U9") (pin "8") (pinfunction "VCC_8") (pintype "passive"))
    )
    (net (code "76") (name "VOUT+3V0") (class "Default")
      (node (ref "P2") (pin "10") (pinfunction "10_10") (pintype "passive"))
      (node (ref "P2") (pin "12") (pinfunction "12_12") (pintype "passive"))
      (node (ref "P2") (pin "8") (pinfunction "8_8") (pintype "passive"))
      (node (ref "R1") (pin "1") (pinfunction "1_1") (pintype "passive"))
      (node (ref "TP19") (pin "1") (pinfunction "1_1") (pintype "passive"))
    )
    (net (code "77") (name "unconnected-(M1-NC-Pad17)") (class "Default")
      (node (ref "M1") (pin "17") (pinfunction "NC_17") (pintype "passive"))
    )
    (net (code "78") (name "unconnected-(P4-Pad1)") (class "Default")
      (node (ref "P4") (pin "1") (pinfunction "1_1") (pintype "passive"))
    )
    (net (code "79") (name "unconnected-(U1-D-Pad4)") (class "Default")
      (node (ref "U1") (pin "4") (pinfunction "D_4") (pintype "passive+no_connect"))
    )
    (net (code "80") (name "unconnected-(U2-NC-Pad6)") (class "Default")
      (node (ref "U2") (pin "6") (pinfunction "NC_6") (pintype "passive+no_connect"))
    )
    (net (code "81") (name "unconnected-(U7-PA6{slash}COM2{slash}ADC_IN0-Pad7)") (class "Default")
      (node (ref "U7") (pin "7") (pinfunction "PA6/COM2/ADC_IN0_7") (pintype "passive"))
    )
    (net (code "82") (name "unconnected-(U7-PA7{slash}SEG0-Pad8)") (class "Default")
      (node (ref "U7") (pin "8") (pinfunction "PA7/SEG0_8") (pintype "passive"))
    )
    (net (code "83") (name "unconnected-(U7-PC7{slash}ADC_IN3-Pad62)") (class "Default")
      (node (ref "U7") (pin "62") (pinfunction "PC7/ADC_IN3_62") (pintype "passive"))
    )
    (net (code "84") (name "unconnected-(U7-PD0{slash}SEG7{slash}ADC_IN22-Pad25)") (class "Default")
      (node (ref "U7") (pin "25") (pinfunction "PD0/SEG7/ADC_IN22_25") (pintype "passive"))
    )
    (net (code "85") (name "unconnected-(U7-PD1{slash}COM3{slash}ADC1_IN21-Pad26)") (class "Default")
      (node (ref "U7") (pin "26") (pinfunction "PD1/COM3/ADC1_IN21_26") (pintype "passive"))
    )
    (net (code "86") (name "unconnected-(U7-PD2{slash}SEG8{slash}ADC_IN20-Pad27)") (class "Default")
      (node (ref "U7") (pin "27") (pinfunction "PD2/SEG8/ADC_IN20_27") (pintype "passive"))
    )
    (net (code "87") (name "unconnected-(U7-PD3{slash}SEG9{slash}ADC_IN19-Pad28)") (class "Default")
      (node (ref "U7") (pin "28") (pinfunction "PD3/SEG9/ADC_IN19_28") (pintype "passive"))
    )
    (net (code "88") (name "unconnected-(U7-PE2{slash}SEG3-Pad21)") (class "Default")
      (node (ref "U7") (pin "21") (pinfunction "PE2/SEG3_21") (pintype "passive"))
    )
    (net (code "89") (name "unconnected-(U7-PE5{slash}SEG6{slash}ADC_IN23-Pad24)") (class "Default")
      (node (ref "U7") (pin "24") (pinfunction "PE5/SEG6/ADC_IN23_24") (pintype "passive"))
    )
    (net (code "90") (name "unconnected-(U7-PE6-Pad63)") (class "Default")
      (node (ref "U7") (pin "63") (pinfunction "PE6_63") (pintype "passive"))
    )
    (net (code "91") (name "unconnected-(U7-PE7-Pad64)") (class "Default")
      (node (ref "U7") (pin "64") (pinfunction "PE7_64") (pintype "passive"))
    )
    (net (code "92") (name "unconnected-(U7-PG3-Pad17)") (class "Default")
      (node (ref "U7") (pin "17") (pinfunction "PG3_17") (pintype "passive"))
    )
    (net (code "93") (name "unconnected-(U7-PG7{slash}SPI2_MISO-Pad52)") (class "Default")
      (node (ref "U7") (pin "52") (pinfunction "PG7/SPI2_MISO_52") (pintype "passive"))
    )
    (net (code "94") (name "unconnected-(U7-VLCD-Pad18)") (class "Default")
      (node (ref "U7") (pin "18") (pinfunction "VLCD_18") (pintype "passive+no_connect"))
    )
  )
)
